# Microcontroller.net
KiCad netlist of a schematic drawn in Altium Designer
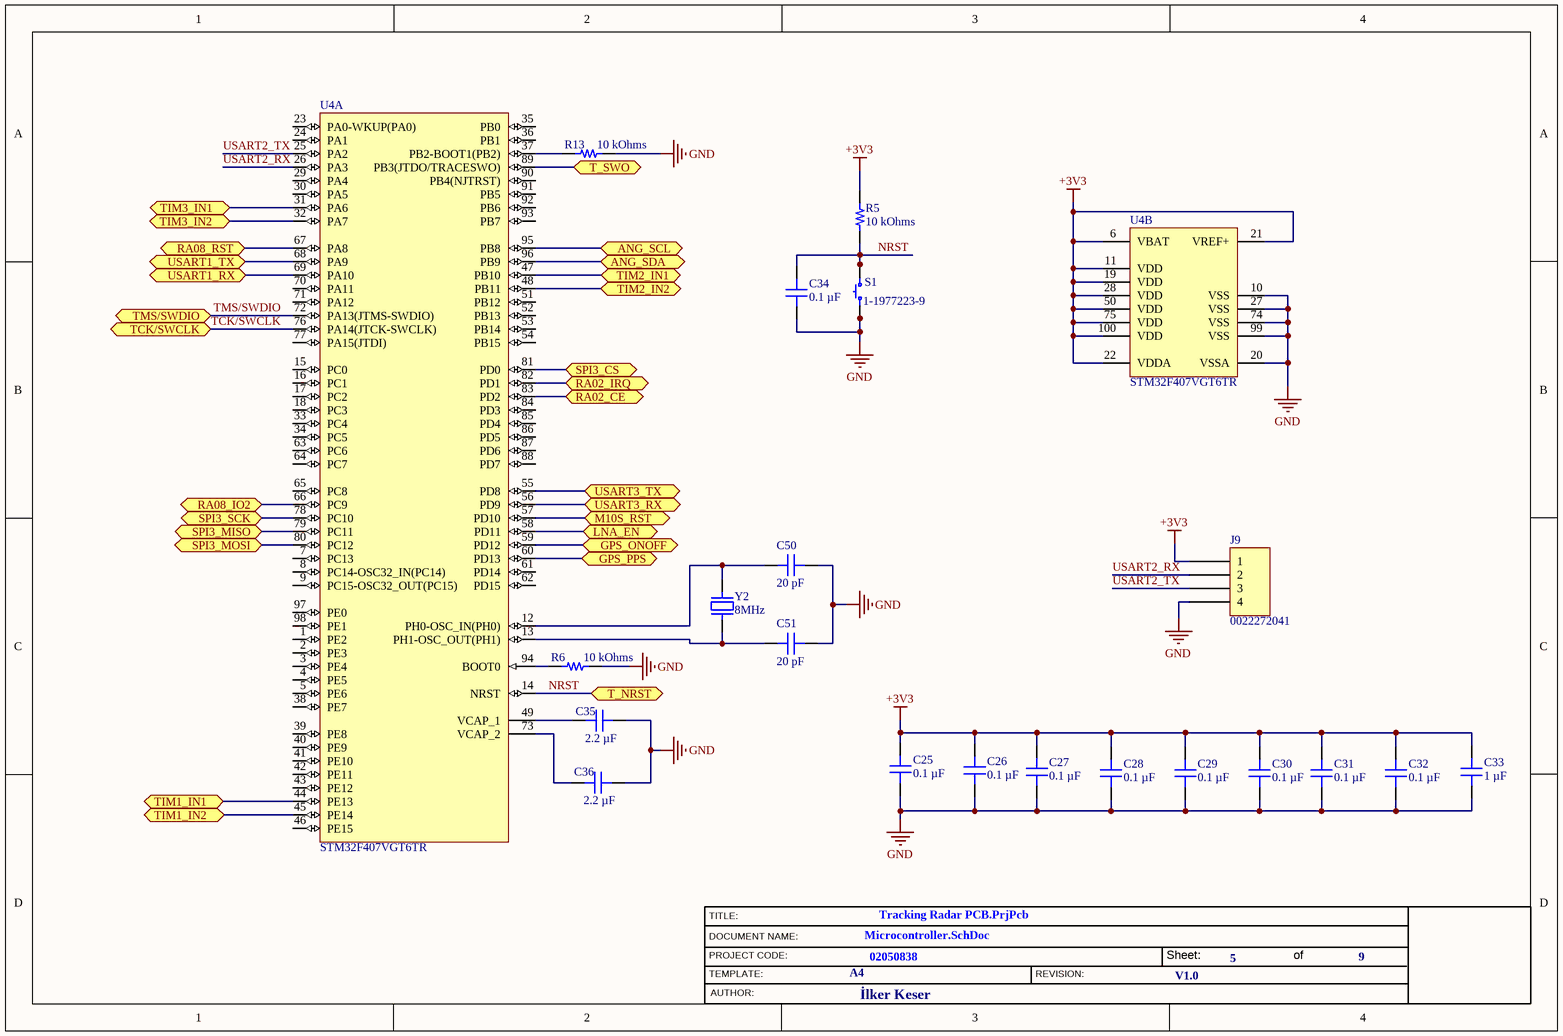
[diagram p0: Microcontroller.SchDoc]

(export (version "E")
  (design (tool "Eeschema 10.0.6"))
  (components
    (comp (ref "C25")
      (value "0.1 µF")
      (footprint "CAP 0402_1005")
      (description "CAP CER 0.1UF 6.3V X5R 0402")
      (fields
        (field (name "PART NUMBER") "C0402C104M9PAC7867")
        (field (name "CAPACITANCE") "0.1 µF")
        (field (name "MANUFACTURER") "KEMET")
      )
      (libsource (lib "Celestial Altium Library - altium_library") (part "Capacitor"))
    )
    (comp (ref "C26")
      (value "0.1 µF")
      (footprint "CAP 0402_1005")
      (description "CAP CER 0.1UF 6.3V X5R 0402")
      (fields
        (field (name "PART NUMBER") "C0402C104M9PAC7867")
        (field (name "CAPACITANCE") "0.1 µF")
        (field (name "MANUFACTURER") "KEMET")
      )
      (libsource (lib "Celestial Altium Library - altium_library") (part "Capacitor"))
    )
    (comp (ref "C27")
      (value "0.1 µF")
      (footprint "CAP 0402_1005")
      (description "CAP CER 0.1UF 6.3V X5R 0402")
      (fields
        (field (name "PART NUMBER") "C0402C104M9PAC7867")
        (field (name "CAPACITANCE") "0.1 µF")
        (field (name "MANUFACTURER") "KEMET")
      )
      (libsource (lib "Celestial Altium Library - altium_library") (part "Capacitor"))
    )
    (comp (ref "C28")
      (value "0.1 µF")
      (footprint "CAP 0402_1005")
      (description "CAP CER 0.1UF 6.3V X5R 0402")
      (fields
        (field (name "PART NUMBER") "C0402C104M9PAC7867")
        (field (name "CAPACITANCE") "0.1 µF")
        (field (name "MANUFACTURER") "KEMET")
      )
      (libsource (lib "Celestial Altium Library - altium_library") (part "Capacitor"))
    )
    (comp (ref "C29")
      (value "0.1 µF")
      (footprint "CAP 0402_1005")
      (description "CAP CER 0.1UF 6.3V X5R 0402")
      (fields
        (field (name "PART NUMBER") "C0402C104M9PAC7867")
        (field (name "CAPACITANCE") "0.1 µF")
        (field (name "MANUFACTURER") "KEMET")
      )
      (libsource (lib "Celestial Altium Library - altium_library") (part "Capacitor"))
    )
    (comp (ref "C30")
      (value "0.1 µF")
      (footprint "CAP 0402_1005")
      (description "CAP CER 0.1UF 6.3V X5R 0402")
      (fields
        (field (name "PART NUMBER") "C0402C104M9PAC7867")
        (field (name "CAPACITANCE") "0.1 µF")
        (field (name "MANUFACTURER") "KEMET")
      )
      (libsource (lib "Celestial Altium Library - altium_library") (part "Capacitor"))
    )
    (comp (ref "C31")
      (value "0.1 µF")
      (footprint "CAP 0402_1005")
      (description "CAP CER 0.1UF 6.3V X5R 0402")
      (fields
        (field (name "PART NUMBER") "C0402C104M9PAC7867")
        (field (name "CAPACITANCE") "0.1 µF")
        (field (name "MANUFACTURER") "KEMET")
      )
      (libsource (lib "Celestial Altium Library - altium_library") (part "Capacitor"))
    )
    (comp (ref "C32")
      (value "0.1 µF")
      (footprint "CAP 0402_1005")
      (description "CAP CER 0.1UF 6.3V X5R 0402")
      (fields
        (field (name "PART NUMBER") "C0402C104M9PAC7867")
        (field (name "CAPACITANCE") "0.1 µF")
        (field (name "MANUFACTURER") "KEMET")
      )
      (libsource (lib "Celestial Altium Library - altium_library") (part "Capacitor"))
    )
    (comp (ref "C33")
      (value "1 µF")
      (footprint "CAP 0402_1005")
      (description "CAP CER 1UF 6.3V X5R 0402")
      (fields
        (field (name "PART NUMBER") "GRM152R60J105ME15D")
        (field (name "CAPACITANCE") "1 µF")
        (field (name "MANUFACTURER") "Murata Electronics")
      )
      (libsource (lib "Celestial Altium Library - altium_library") (part "Capacitor"))
    )
    (comp (ref "C34")
      (value "0.1 µF")
      (footprint "CAP 0402_1005")
      (description "CAP CER 0.1UF 6.3V X5R 0402")
      (fields
        (field (name "PART NUMBER") "C0402C104M9PAC7867")
        (field (name "CAPACITANCE") "0.1 µF")
        (field (name "MANUFACTURER") "KEMET")
      )
      (libsource (lib "Celestial Altium Library - altium_library") (part "Capacitor"))
    )
    (comp (ref "C35")
      (value "2.2 µF")
      (footprint "CAP 0402_1005")
      (description "CAP CER 2.2UF 10V X5R 0402")
      (fields
        (field (name "PART NUMBER") "885012105013")
        (field (name "CAPACITANCE") "2.2 µF")
        (field (name "MANUFACTURER") "Würth Elektronik")
      )
      (libsource (lib "Celestial Altium Library - altium_library") (part "Capacitor"))
    )
    (comp (ref "C36")
      (value "2.2 µF")
      (footprint "CAP 0402_1005")
      (description "CAP CER 2.2UF 10V X5R 0402")
      (fields
        (field (name "PART NUMBER") "885012105013")
        (field (name "CAPACITANCE") "2.2 µF")
        (field (name "MANUFACTURER") "Würth Elektronik")
      )
      (libsource (lib "Celestial Altium Library - altium_library") (part "Capacitor"))
    )
    (comp (ref "C50")
      (value "20 pF")
      (footprint "CAP 0603_1608")
      (description "CAP CER 20PF 10V X8R 0603")
      (fields
        (field (name "PART NUMBER") "C0603C200G8HAC7867")
        (field (name "CAPACITANCE") "20 pF")
        (field (name "MANUFACTURER") "KEMET")
      )
      (libsource (lib "Celestial Altium Library - altium_library") (part "Capacitor"))
    )
    (comp (ref "C51")
      (value "20 pF")
      (footprint "CAP 0603_1608")
      (description "CAP CER 20PF 10V X8R 0603")
      (fields
        (field (name "PART NUMBER") "C0603C200G8HAC7867")
        (field (name "CAPACITANCE") "20 pF")
        (field (name "MANUFACTURER") "KEMET")
      )
      (libsource (lib "Celestial Altium Library - altium_library") (part "Capacitor"))
    )
    (comp (ref "J9")
      (value "0022272041")
      (footprint "MOLEX KK 0022272041")
      (description "CONN HEADER VERT 4POS 2.54MM")
      (fields (field (name "MANUFACTURER") "Molex"))
      (libsource (lib "Celestial Altium Library - altium_library") (part "4 Pin"))
    )
    (comp (ref "R5")
      (value "10 kOhms")
      (footprint "KOA RES RK73 RN73 0402_1005")
      (description "RES 10K OHM 0.5% 1/10W 0402")
      (fields
        (field (name "PART NUMBER") "RK73H1ETTP1002D")
        (field (name "MANUFACTURER") "KOA Speer Electronics, Inc.")
      )
      (libsource (lib "Celestial Altium Library - altium_library") (part "Resistor"))
    )
    (comp (ref "R6")
      (value "10 kOhms")
      (footprint "YAGEO RES 0402_1005")
      (description "RES 10K OHM 0.1% 1/16W 0402")
      (fields (field (name "PART NUMBER") "RP0402BRD0710KL") (field (name "MANUFACTURER") "Yageo"))
      (libsource (lib "Celestial Altium Library - altium_library") (part "Resistor"))
    )
    (comp (ref "R13")
      (value "10 kOhms")
      (footprint "YAGEO RES 0402_1005")
      (description "RES 10K OHM 0.1% 1/16W 0402")
      (fields (field (name "PART NUMBER") "RP0402BRD0710KL") (field (name "MANUFACTURER") "Yageo"))
      (libsource (lib "Celestial Altium Library - altium_library") (part "Resistor"))
    )
    (comp (ref "S1")
      (value "1-1977223-9")
      (footprint "TE FSM6JSMA")
      (description "SWITCH TACTILE SPST-NO 0.05A 24V")
      (fields (field (name "MANUFACTURER") "TE Connectivity ALCOSWITCH Switches"))
      (libsource (lib "Celestial Altium Library - altium_library") (part "SPST-NO 4 PIN"))
    )
    (comp (ref "U4")
      (value "STM32F407VGT6TR")
      (footprint "STM-LQFP100_N")
      (fields (field (name "MANUFACTURER") "STMicroelectronics"))
      (libsource (lib "STMicroelectronics STM32 F4") (part "STM32F407VGT6TR"))
    )
    (comp (ref "Y2")
      (value "8MHz")
      (footprint "TXC 9C")
      (description "CRYSTAL 8.0000MHZ 20PF SMD")
      (fields (field (name "PART NUMBER") "9C-8.000MBBK-T") (field (name "MANUFACTURER") "TXC CORPORATION"))
      (libsource (lib "Celestial Altium Library - altium_library") (part "TXC Crystal 9C"))
    )
  )
  (nets
    (net (code "1") (name "+3V3") (class "Default")
      (node (ref "C25") (pin "2") (pinfunction "2_2") (pintype "passive"))
      (node (ref "C26") (pin "2") (pinfunction "2_2") (pintype "passive"))
      (node (ref "C27") (pin "2") (pinfunction "2_2") (pintype "passive"))
      (node (ref "C28") (pin "2") (pinfunction "2_2") (pintype "passive"))
      (node (ref "C29") (pin "2") (pinfunction "2_2") (pintype "passive"))
      (node (ref "C30") (pin "2") (pinfunction "2_2") (pintype "passive"))
      (node (ref "C31") (pin "2") (pinfunction "2_2") (pintype "passive"))
      (node (ref "C32") (pin "2") (pinfunction "2_2") (pintype "passive"))
      (node (ref "C33") (pin "2") (pinfunction "2_2") (pintype "passive"))
      (node (ref "J9") (pin "1") (pinfunction "1_1") (pintype "passive"))
      (node (ref "R5") (pin "1") (pinfunction "1_1") (pintype "passive"))
      (node (ref "U4") (pin "100") (pinfunction "VDD_100") (pintype "power_in"))
      (node (ref "U4") (pin "11") (pinfunction "VDD_11") (pintype "power_in"))
      (node (ref "U4") (pin "19") (pinfunction "VDD_19") (pintype "power_in"))
      (node (ref "U4") (pin "21") (pinfunction "VREF+_21") (pintype "power_in"))
      (node (ref "U4") (pin "22") (pinfunction "VDDA_22") (pintype "power_in"))
      (node (ref "U4") (pin "28") (pinfunction "VDD_28") (pintype "power_in"))
      (node (ref "U4") (pin "50") (pinfunction "VDD_50") (pintype "power_in"))
      (node (ref "U4") (pin "6") (pinfunction "VBAT_6") (pintype "power_in"))
      (node (ref "U4") (pin "75") (pinfunction "VDD_75") (pintype "power_in"))
    )
    (net (code "2") (name "/ANG_SCL") (class "Default")
      (node (ref "U4") (pin "95") (pinfunction "PB8_95") (pintype "bidirectional"))
    )
    (net (code "3") (name "/ANG_SDA") (class "Default")
      (node (ref "U4") (pin "96") (pinfunction "PB9_96") (pintype "bidirectional"))
    )
    (net (code "4") (name "/GPS_ONOFF") (class "Default")
      (node (ref "U4") (pin "59") (pinfunction "PD12_59") (pintype "bidirectional"))
    )
    (net (code "5") (name "/GPS_PPS") (class "Default")
      (node (ref "U4") (pin "60") (pinfunction "PD13_60") (pintype "bidirectional"))
    )
    (net (code "6") (name "/LNA_EN") (class "Default")
      (node (ref "U4") (pin "58") (pinfunction "PD11_58") (pintype "bidirectional"))
    )
    (net (code "7") (name "/M10S_RST") (class "Default")
      (node (ref "U4") (pin "57") (pinfunction "PD10_57") (pintype "bidirectional"))
    )
    (net (code "8") (name "/NRST") (class "Default")
      (node (ref "C34") (pin "2") (pinfunction "2_2") (pintype "passive"))
      (node (ref "R5") (pin "2") (pinfunction "2_2") (pintype "passive"))
      (node (ref "S1") (pin "3") (pinfunction "3_3") (pintype "passive"))
      (node (ref "S1") (pin "4") (pinfunction "4_4") (pintype "passive"))
      (node (ref "U4") (pin "14") (pinfunction "NRST_14") (pintype "bidirectional"))
    )
    (net (code "9") (name "/RA02_CE") (class "Default")
      (node (ref "U4") (pin "83") (pinfunction "PD2_83") (pintype "bidirectional"))
    )
    (net (code "10") (name "/RA02_IRQ") (class "Default")
      (node (ref "U4") (pin "82") (pinfunction "PD1_82") (pintype "bidirectional"))
    )
    (net (code "11") (name "/RA08_IO2") (class "Default")
      (node (ref "U4") (pin "66") (pinfunction "PC9_66") (pintype "bidirectional"))
    )
    (net (code "12") (name "/RA08_RST") (class "Default")
      (node (ref "U4") (pin "67") (pinfunction "PA8_67") (pintype "bidirectional"))
    )
    (net (code "13") (name "/SPI3_CS") (class "Default")
      (node (ref "U4") (pin "81") (pinfunction "PD0_81") (pintype "bidirectional"))
    )
    (net (code "14") (name "/SPI3_MISO") (class "Default")
      (node (ref "U4") (pin "79") (pinfunction "PC11_79") (pintype "bidirectional"))
    )
    (net (code "15") (name "/SPI3_MOSI") (class "Default")
      (node (ref "U4") (pin "80") (pinfunction "PC12_80") (pintype "bidirectional"))
    )
    (net (code "16") (name "/SPI3_SCK") (class "Default")
      (node (ref "U4") (pin "78") (pinfunction "PC10_78") (pintype "bidirectional"))
    )
    (net (code "17") (name "/TCK{slash}SWCLK") (class "Default")
      (node (ref "U4") (pin "76") (pinfunction "PA14(JTCK-SWCLK)_76") (pintype "bidirectional"))
    )
    (net (code "18") (name "/TIM1_IN1") (class "Default")
      (node (ref "U4") (pin "44") (pinfunction "PE13_44") (pintype "bidirectional"))
    )
    (net (code "19") (name "/TIM1_IN2") (class "Default")
      (node (ref "U4") (pin "45") (pinfunction "PE14_45") (pintype "bidirectional"))
    )
    (net (code "20") (name "/TIM2_IN1") (class "Default")
      (node (ref "U4") (pin "47") (pinfunction "PB10_47") (pintype "bidirectional"))
    )
    (net (code "21") (name "/TIM2_IN2") (class "Default")
      (node (ref "U4") (pin "48") (pinfunction "PB11_48") (pintype "bidirectional"))
    )
    (net (code "22") (name "/TIM3_IN1") (class "Default")
      (node (ref "U4") (pin "31") (pinfunction "PA6_31") (pintype "bidirectional"))
    )
    (net (code "23") (name "/TIM3_IN2") (class "Default")
      (node (ref "U4") (pin "32") (pinfunction "PA7_32") (pintype "bidirectional"))
    )
    (net (code "24") (name "/TMS{slash}SWDIO") (class "Default")
      (node (ref "U4") (pin "72") (pinfunction "PA13(JTMS-SWDIO)_72") (pintype "bidirectional"))
    )
    (net (code "25") (name "/T_SWO") (class "Default")
      (node (ref "U4") (pin "89") (pinfunction "PB3(JTDO/TRACESWO)_89") (pintype "bidirectional"))
    )
    (net (code "26") (name "/USART1_RX") (class "Default")
      (node (ref "U4") (pin "69") (pinfunction "PA10_69") (pintype "bidirectional"))
    )
    (net (code "27") (name "/USART1_TX") (class "Default")
      (node (ref "U4") (pin "68") (pinfunction "PA9_68") (pintype "bidirectional"))
    )
    (net (code "28") (name "/USART2_RX") (class "Default")
      (node (ref "J9") (pin "2") (pinfunction "2_2") (pintype "passive"))
      (node (ref "U4") (pin "26") (pinfunction "PA3_26") (pintype "bidirectional"))
    )
    (net (code "29") (name "/USART2_TX") (class "Default")
      (node (ref "J9") (pin "3") (pinfunction "3_3") (pintype "passive"))
      (node (ref "U4") (pin "25") (pinfunction "PA2_25") (pintype "bidirectional"))
    )
    (net (code "30") (name "/USART3_RX") (class "Default")
      (node (ref "U4") (pin "56") (pinfunction "PD9_56") (pintype "bidirectional"))
    )
    (net (code "31") (name "/USART3_TX") (class "Default")
      (node (ref "U4") (pin "55") (pinfunction "PD8_55") (pintype "bidirectional"))
    )
    (net (code "32") (name "GND") (class "Default")
      (node (ref "C25") (pin "1") (pinfunction "1_1") (pintype "passive"))
      (node (ref "C26") (pin "1") (pinfunction "1_1") (pintype "passive"))
      (node (ref "C27") (pin "1") (pinfunction "1_1") (pintype "passive"))
      (node (ref "C28") (pin "1") (pinfunction "1_1") (pintype "passive"))
      (node (ref "C29") (pin "1") (pinfunction "1_1") (pintype "passive"))
      (node (ref "C30") (pin "1") (pinfunction "1_1") (pintype "passive"))
      (node (ref "C31") (pin "1") (pinfunction "1_1") (pintype "passive"))
      (node (ref "C32") (pin "1") (pinfunction "1_1") (pintype "passive"))
      (node (ref "C33") (pin "1") (pinfunction "1_1") (pintype "passive"))
      (node (ref "C34") (pin "1") (pinfunction "1_1") (pintype "passive"))
      (node (ref "C35") (pin "2") (pinfunction "2_2") (pintype "passive"))
      (node (ref "C36") (pin "2") (pinfunction "2_2") (pintype "passive"))
      (node (ref "C50") (pin "2") (pinfunction "2_2") (pintype "passive"))
      (node (ref "C51") (pin "2") (pinfunction "2_2") (pintype "passive"))
      (node (ref "J9") (pin "4") (pinfunction "4_4") (pintype "passive"))
      (node (ref "R13") (pin "2") (pinfunction "2_2") (pintype "passive"))
      (node (ref "R6") (pin "2") (pinfunction "2_2") (pintype "passive"))
      (node (ref "S1") (pin "1") (pinfunction "1_1") (pintype "passive"))
      (node (ref "S1") (pin "2") (pinfunction "2_2") (pintype "passive"))
      (node (ref "U4") (pin "10") (pinfunction "VSS_10") (pintype "power_in"))
      (node (ref "U4") (pin "20") (pinfunction "VSSA_20") (pintype "power_in"))
      (node (ref "U4") (pin "27") (pinfunction "VSS_27") (pintype "power_in"))
      (node (ref "U4") (pin "74") (pinfunction "VSS_74") (pintype "power_in"))
      (node (ref "U4") (pin "99") (pinfunction "VSS_99") (pintype "power_in"))
    )
    (net (code "33") (name "Net-(U4A-BOOT0)") (class "Default")
      (node (ref "R6") (pin "1") (pinfunction "1_1") (pintype "passive"))
      (node (ref "U4") (pin "94") (pinfunction "BOOT0_94") (pintype "input"))
    )
    (net (code "34") (name "Net-(U4A-PB2-BOOT1(PB2))") (class "Default")
      (node (ref "R13") (pin "1") (pinfunction "1_1") (pintype "passive"))
      (node (ref "U4") (pin "37") (pinfunction "PB2-BOOT1(PB2)_37") (pintype "bidirectional"))
    )
    (net (code "35") (name "Net-(U4A-PH0-OSC_IN(PH0))") (class "Default")
      (node (ref "C50") (pin "1") (pinfunction "1_1") (pintype "passive"))
      (node (ref "U4") (pin "12") (pinfunction "PH0-OSC_IN(PH0)_12") (pintype "bidirectional"))
      (node (ref "Y2") (pin "2") (pinfunction "2_2") (pintype "passive"))
    )
    (net (code "36") (name "Net-(U4A-PH1-OSC_OUT(PH1))") (class "Default")
      (node (ref "C51") (pin "1") (pinfunction "1_1") (pintype "passive"))
      (node (ref "U4") (pin "13") (pinfunction "PH1-OSC_OUT(PH1)_13") (pintype "bidirectional"))
      (node (ref "Y2") (pin "1") (pinfunction "1_1") (pintype "passive"))
    )
    (net (code "37") (name "Net-(U4A-VCAP_1)") (class "Default")
      (node (ref "C35") (pin "1") (pinfunction "1_1") (pintype "passive"))
      (node (ref "U4") (pin "49") (pinfunction "VCAP_1_49") (pintype "power_in"))
    )
    (net (code "38") (name "Net-(U4A-VCAP_2)") (class "Default")
      (node (ref "C36") (pin "1") (pinfunction "1_1") (pintype "passive"))
      (node (ref "U4") (pin "73") (pinfunction "VCAP_2_73") (pintype "power_in"))
    )
    (net (code "39") (name "unconnected-(U4A-PA0-WKUP(PA0)-Pad23)") (class "Default")
      (node (ref "U4") (pin "23") (pinfunction "PA0-WKUP(PA0)_23") (pintype "bidirectional"))
    )
    (net (code "40") (name "unconnected-(U4A-PA1-Pad24)") (class "Default")
      (node (ref "U4") (pin "24") (pinfunction "PA1_24") (pintype "bidirectional"))
    )
    (net (code "41") (name "unconnected-(U4A-PA4-Pad29)") (class "Default")
      (node (ref "U4") (pin "29") (pinfunction "PA4_29") (pintype "bidirectional"))
    )
    (net (code "42") (name "unconnected-(U4A-PA5-Pad30)") (class "Default")
      (node (ref "U4") (pin "30") (pinfunction "PA5_30") (pintype "bidirectional"))
    )
    (net (code "43") (name "unconnected-(U4A-PA11-Pad70)") (class "Default")
      (node (ref "U4") (pin "70") (pinfunction "PA11_70") (pintype "bidirectional"))
    )
    (net (code "44") (name "unconnected-(U4A-PA12-Pad71)") (class "Default")
      (node (ref "U4") (pin "71") (pinfunction "PA12_71") (pintype "bidirectional"))
    )
    (net (code "45") (name "unconnected-(U4A-PA15(JTDI)-Pad77)") (class "Default")
      (node (ref "U4") (pin "77") (pinfunction "PA15(JTDI)_77") (pintype "bidirectional"))
    )
    (net (code "46") (name "unconnected-(U4A-PB0-Pad35)") (class "Default")
      (node (ref "U4") (pin "35") (pinfunction "PB0_35") (pintype "bidirectional"))
    )
    (net (code "47") (name "unconnected-(U4A-PB1-Pad36)") (class "Default")
      (node (ref "U4") (pin "36") (pinfunction "PB1_36") (pintype "bidirectional"))
    )
    (net (code "48") (name "unconnected-(U4A-PB4(NJTRST)-Pad90)") (class "Default")
      (node (ref "U4") (pin "90") (pinfunction "PB4(NJTRST)_90") (pintype "bidirectional"))
    )
    (net (code "49") (name "unconnected-(U4A-PB5-Pad91)") (class "Default")
      (node (ref "U4") (pin "91") (pinfunction "PB5_91") (pintype "bidirectional"))
    )
    (net (code "50") (name "unconnected-(U4A-PB6-Pad92)") (class "Default")
      (node (ref "U4") (pin "92") (pinfunction "PB6_92") (pintype "bidirectional"))
    )
    (net (code "51") (name "unconnected-(U4A-PB7-Pad93)") (class "Default")
      (node (ref "U4") (pin "93") (pinfunction "PB7_93") (pintype "bidirectional"))
    )
    (net (code "52") (name "unconnected-(U4A-PB12-Pad51)") (class "Default")
      (node (ref "U4") (pin "51") (pinfunction "PB12_51") (pintype "bidirectional"))
    )
    (net (code "53") (name "unconnected-(U4A-PB13-Pad52)") (class "Default")
      (node (ref "U4") (pin "52") (pinfunction "PB13_52") (pintype "bidirectional"))
    )
    (net (code "54") (name "unconnected-(U4A-PB14-Pad53)") (class "Default")
      (node (ref "U4") (pin "53") (pinfunction "PB14_53") (pintype "bidirectional"))
    )
    (net (code "55") (name "unconnected-(U4A-PB15-Pad54)") (class "Default")
      (node (ref "U4") (pin "54") (pinfunction "PB15_54") (pintype "bidirectional"))
    )
    (net (code "56") (name "unconnected-(U4A-PC0-Pad15)") (class "Default")
      (node (ref "U4") (pin "15") (pinfunction "PC0_15") (pintype "bidirectional"))
    )
    (net (code "57") (name "unconnected-(U4A-PC1-Pad16)") (class "Default")
      (node (ref "U4") (pin "16") (pinfunction "PC1_16") (pintype "bidirectional"))
    )
    (net (code "58") (name "unconnected-(U4A-PC2-Pad17)") (class "Default")
      (node (ref "U4") (pin "17") (pinfunction "PC2_17") (pintype "bidirectional"))
    )
    (net (code "59") (name "unconnected-(U4A-PC3-Pad18)") (class "Default")
      (node (ref "U4") (pin "18") (pinfunction "PC3_18") (pintype "bidirectional"))
    )
    (net (code "60") (name "unconnected-(U4A-PC4-Pad33)") (class "Default")
      (node (ref "U4") (pin "33") (pinfunction "PC4_33") (pintype "bidirectional"))
    )
    (net (code "61") (name "unconnected-(U4A-PC5-Pad34)") (class "Default")
      (node (ref "U4") (pin "34") (pinfunction "PC5_34") (pintype "bidirectional"))
    )
    (net (code "62") (name "unconnected-(U4A-PC6-Pad63)") (class "Default")
      (node (ref "U4") (pin "63") (pinfunction "PC6_63") (pintype "bidirectional"))
    )
    (net (code "63") (name "unconnected-(U4A-PC7-Pad64)") (class "Default")
      (node (ref "U4") (pin "64") (pinfunction "PC7_64") (pintype "bidirectional"))
    )
    (net (code "64") (name "unconnected-(U4A-PC8-Pad65)") (class "Default")
      (node (ref "U4") (pin "65") (pinfunction "PC8_65") (pintype "bidirectional"))
    )
    (net (code "65") (name "unconnected-(U4A-PC13-Pad7)") (class "Default")
      (node (ref "U4") (pin "7") (pinfunction "PC13_7") (pintype "bidirectional"))
    )
    (net (code "66") (name "unconnected-(U4A-PC14-OSC32_IN(PC14)-Pad8)") (class "Default")
      (node (ref "U4") (pin "8") (pinfunction "PC14-OSC32_IN(PC14)_8") (pintype "bidirectional"))
    )
    (net (code "67") (name "unconnected-(U4A-PC15-OSC32_OUT(PC15)-Pad9)") (class "Default")
      (node (ref "U4") (pin "9") (pinfunction "PC15-OSC32_OUT(PC15)_9") (pintype "bidirectional"))
    )
    (net (code "68") (name "unconnected-(U4A-PD3-Pad84)") (class "Default")
      (node (ref "U4") (pin "84") (pinfunction "PD3_84") (pintype "bidirectional"))
    )
    (net (code "69") (name "unconnected-(U4A-PD4-Pad85)") (class "Default")
      (node (ref "U4") (pin "85") (pinfunction "PD4_85") (pintype "bidirectional"))
    )
    (net (code "70") (name "unconnected-(U4A-PD5-Pad86)") (class "Default")
      (node (ref "U4") (pin "86") (pinfunction "PD5_86") (pintype "bidirectional"))
    )
    (net (code "71") (name "unconnected-(U4A-PD6-Pad87)") (class "Default")
      (node (ref "U4") (pin "87") (pinfunction "PD6_87") (pintype "bidirectional"))
    )
    (net (code "72") (name "unconnected-(U4A-PD7-Pad88)") (class "Default")
      (node (ref "U4") (pin "88") (pinfunction "PD7_88") (pintype "bidirectional"))
    )
    (net (code "73") (name "unconnected-(U4A-PD14-Pad61)") (class "Default")
      (node (ref "U4") (pin "61") (pinfunction "PD14_61") (pintype "bidirectional"))
    )
    (net (code "74") (name "unconnected-(U4A-PD15-Pad62)") (class "Default")
      (node (ref "U4") (pin "62") (pinfunction "PD15_62") (pintype "bidirectional"))
    )
    (net (code "75") (name "unconnected-(U4A-PE0-Pad97)") (class "Default")
      (node (ref "U4") (pin "97") (pinfunction "PE0_97") (pintype "bidirectional"))
    )
    (net (code "76") (name "unconnected-(U4A-PE1-Pad98)") (class "Default")
      (node (ref "U4") (pin "98") (pinfunction "PE1_98") (pintype "bidirectional"))
    )
    (net (code "77") (name "unconnected-(U4A-PE2-Pad1)") (class "Default")
      (node (ref "U4") (pin "1") (pinfunction "PE2_1") (pintype "bidirectional"))
    )
    (net (code "78") (name "unconnected-(U4A-PE3-Pad2)") (class "Default")
      (node (ref "U4") (pin "2") (pinfunction "PE3_2") (pintype "bidirectional"))
    )
    (net (code "79") (name "unconnected-(U4A-PE4-Pad3)") (class "Default")
      (node (ref "U4") (pin "3") (pinfunction "PE4_3") (pintype "bidirectional"))
    )
    (net (code "80") (name "unconnected-(U4A-PE5-Pad4)") (class "Default")
      (node (ref "U4") (pin "4") (pinfunction "PE5_4") (pintype "bidirectional"))
    )
    (net (code "81") (name "unconnected-(U4A-PE6-Pad5)") (class "Default")
      (node (ref "U4") (pin "5") (pinfunction "PE6_5") (pintype "bidirectional"))
    )
    (net (code "82") (name "unconnected-(U4A-PE7-Pad38)") (class "Default")
      (node (ref "U4") (pin "38") (pinfunction "PE7_38") (pintype "bidirectional"))
    )
    (net (code "83") (name "unconnected-(U4A-PE8-Pad39)") (class "Default")
      (node (ref "U4") (pin "39") (pinfunction "PE8_39") (pintype "bidirectional"))
    )
    (net (code "84") (name "unconnected-(U4A-PE9-Pad40)") (class "Default")
      (node (ref "U4") (pin "40") (pinfunction "PE9_40") (pintype "bidirectional"))
    )
    (net (code "85") (name "unconnected-(U4A-PE10-Pad41)") (class "Default")
      (node (ref "U4") (pin "41") (pinfunction "PE10_41") (pintype "bidirectional"))
    )
    (net (code "86") (name "unconnected-(U4A-PE11-Pad42)") (class "Default")
      (node (ref "U4") (pin "42") (pinfunction "PE11_42") (pintype "bidirectional"))
    )
    (net (code "87") (name "unconnected-(U4A-PE12-Pad43)") (class "Default")
      (node (ref "U4") (pin "43") (pinfunction "PE12_43") (pintype "bidirectional"))
    )
    (net (code "88") (name "unconnected-(U4A-PE15-Pad46)") (class "Default")
      (node (ref "U4") (pin "46") (pinfunction "PE15_46") (pintype "bidirectional"))
    )
  )
)
